# DLPG_main_v3.net
KiCad netlist of a schematic drawn in EAGLE
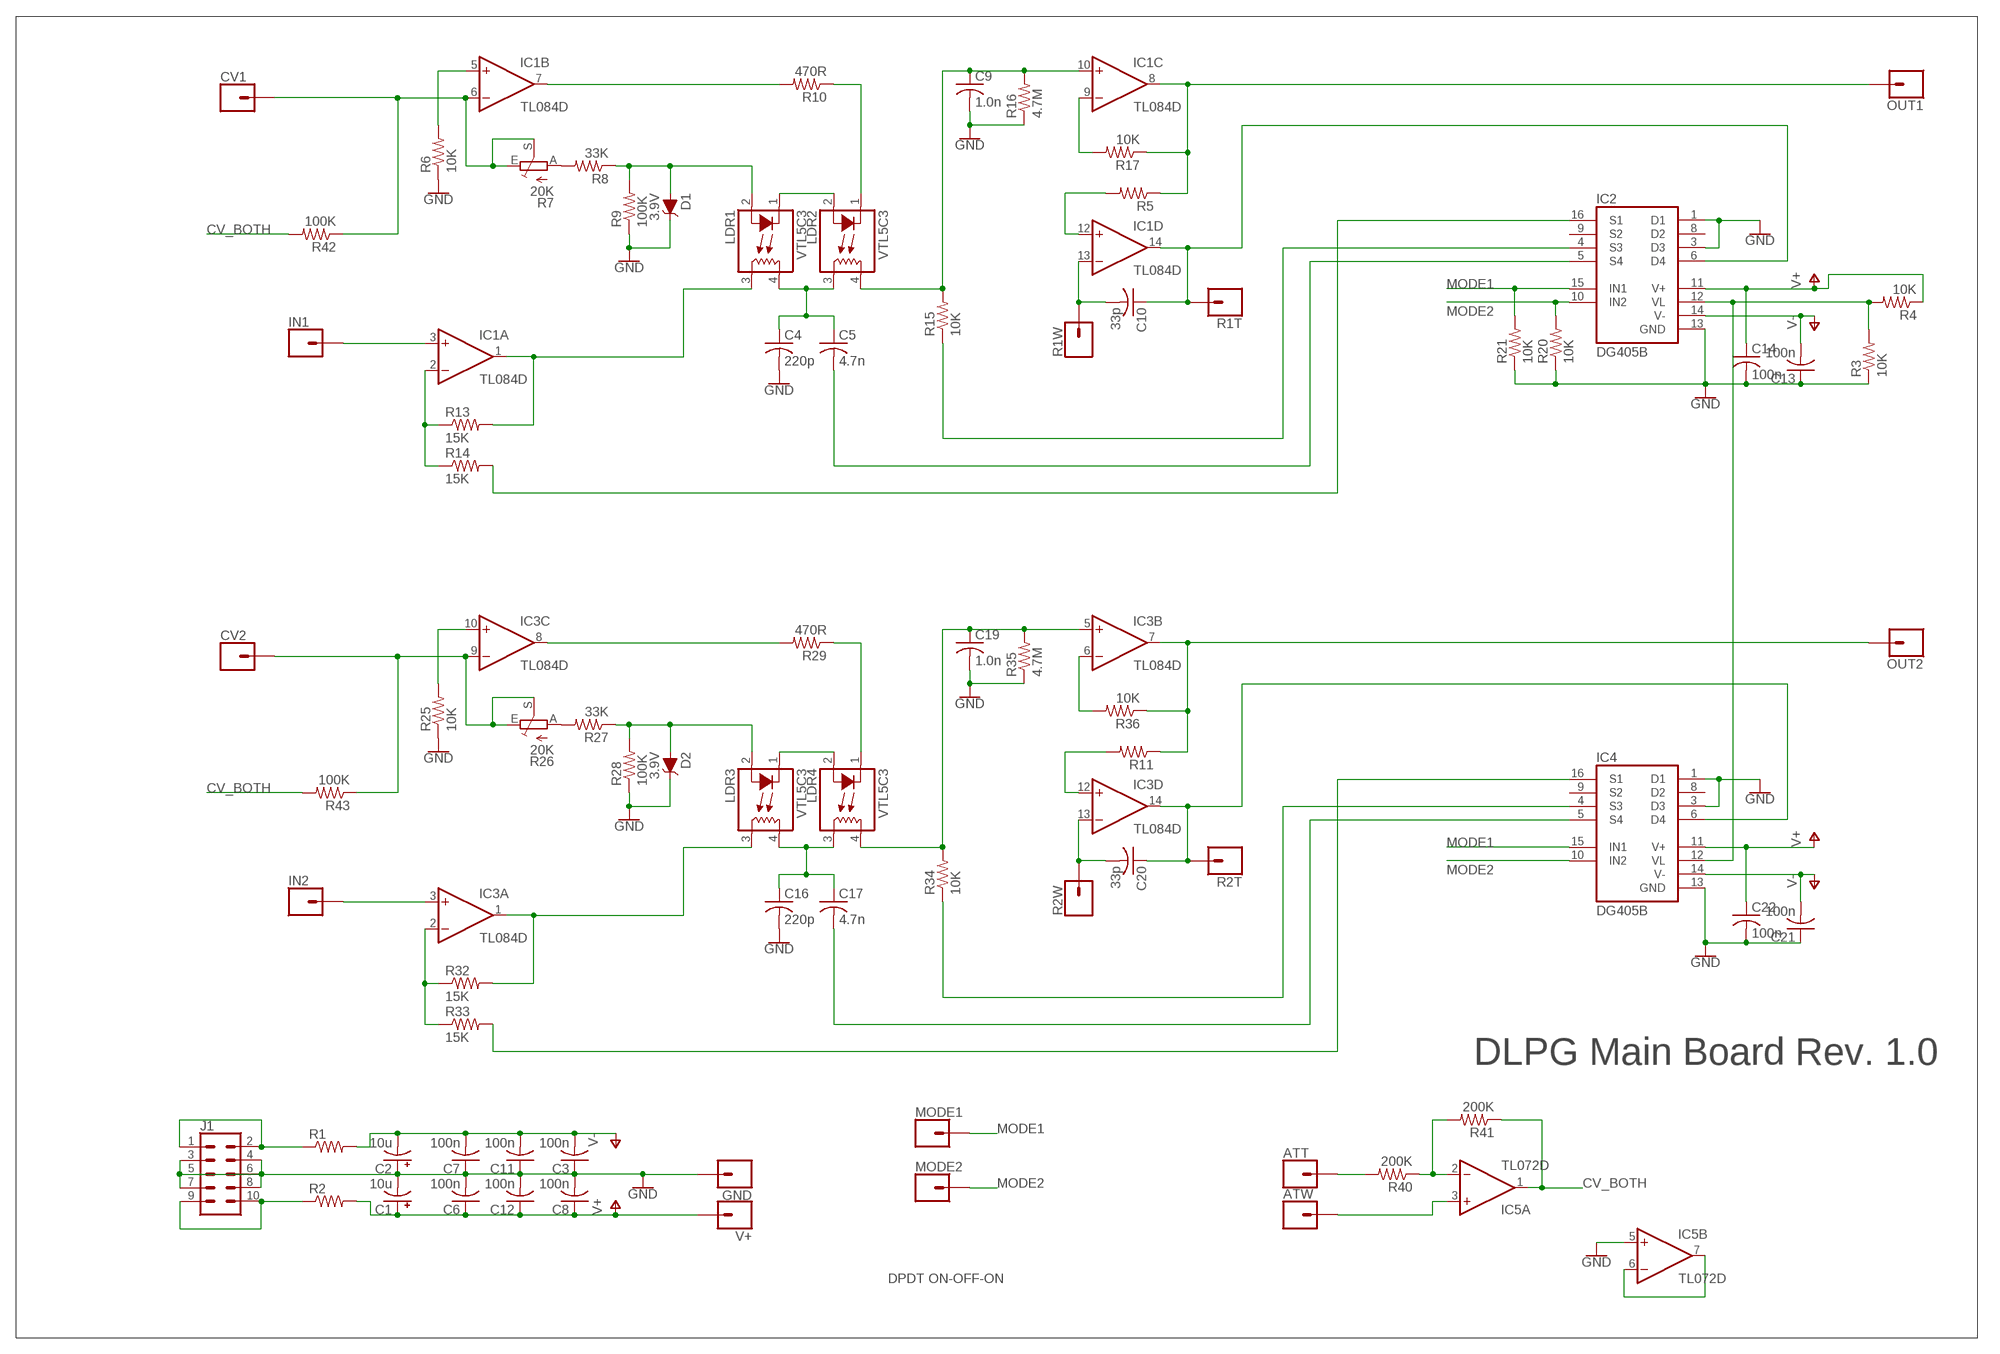
[diagram p0: schematic, sheet 1]

(export (version "E")
  (design (tool "Eeschema 10.0.6"))
  (components
    (comp (ref "ATT")
      (value "CONN_01")
      (footprint "eagle-import:1X01")
      (libsource (lib "eagle-import") (part "CONN_01"))
    )
    (comp (ref "ATW")
      (value "CONN_01")
      (footprint "eagle-import:1X01")
      (libsource (lib "eagle-import") (part "CONN_01"))
    )
    (comp (ref "C1")
      (value "10u")
      (footprint "eagle-import:PANASONIC_C")
      (libsource (lib "eagle-import") (part "CAP_POLC"))
    )
    (comp (ref "C2")
      (value "10u")
      (footprint "eagle-import:PANASONIC_C")
      (libsource (lib "eagle-import") (part "CAP_POLC"))
    )
    (comp (ref "C3")
      (value "100n")
      (footprint "eagle-import:C0805K")
      (libsource (lib "eagle-import") (part "C-USC0805K"))
    )
    (comp (ref "C4")
      (value "220p")
      (footprint "eagle-import:C0805K")
      (libsource (lib "eagle-import") (part "C-USC0805K"))
    )
    (comp (ref "C5")
      (value "4.7n")
      (footprint "eagle-import:C0805K")
      (libsource (lib "eagle-import") (part "C-USC0805K"))
    )
    (comp (ref "C6")
      (value "100n")
      (footprint "eagle-import:C0805K")
      (libsource (lib "eagle-import") (part "C-USC0805K"))
    )
    (comp (ref "C7")
      (value "100n")
      (footprint "eagle-import:C0805K")
      (libsource (lib "eagle-import") (part "C-USC0805K"))
    )
    (comp (ref "C8")
      (value "100n")
      (footprint "eagle-import:C0805K")
      (libsource (lib "eagle-import") (part "C-USC0805K"))
    )
    (comp (ref "C9")
      (value "1.0n")
      (footprint "eagle-import:C0805K")
      (libsource (lib "eagle-import") (part "C-USC0805K"))
    )
    (comp (ref "C10")
      (value "33p")
      (footprint "eagle-import:C0805K")
      (libsource (lib "eagle-import") (part "C-USC0805K"))
    )
    (comp (ref "C11")
      (value "100n")
      (footprint "eagle-import:C0805K")
      (libsource (lib "eagle-import") (part "C-USC0805K"))
    )
    (comp (ref "C12")
      (value "100n")
      (footprint "eagle-import:C0805K")
      (libsource (lib "eagle-import") (part "C-USC0805K"))
    )
    (comp (ref "C13")
      (value "100n")
      (footprint "eagle-import:C0805K")
      (libsource (lib "eagle-import") (part "C-USC0805K"))
    )
    (comp (ref "C14")
      (value "100n")
      (footprint "eagle-import:C0805K")
      (libsource (lib "eagle-import") (part "C-USC0805K"))
    )
    (comp (ref "C16")
      (value "220p")
      (footprint "eagle-import:C0805K")
      (libsource (lib "eagle-import") (part "C-USC0805K"))
    )
    (comp (ref "C17")
      (value "4.7n")
      (footprint "eagle-import:C0805K")
      (libsource (lib "eagle-import") (part "C-USC0805K"))
    )
    (comp (ref "C19")
      (value "1.0n")
      (footprint "eagle-import:C0805K")
      (libsource (lib "eagle-import") (part "C-USC0805K"))
    )
    (comp (ref "C20")
      (value "33p")
      (footprint "eagle-import:C0805K")
      (libsource (lib "eagle-import") (part "C-USC0805K"))
    )
    (comp (ref "C21")
      (value "100n")
      (footprint "eagle-import:C0805K")
      (libsource (lib "eagle-import") (part "C-USC0805K"))
    )
    (comp (ref "C22")
      (value "100n")
      (footprint "eagle-import:C0805K")
      (libsource (lib "eagle-import") (part "C-USC0805K"))
    )
    (comp (ref "CV1")
      (value "CONN_01")
      (footprint "eagle-import:1X01")
      (libsource (lib "eagle-import") (part "CONN_01"))
    )
    (comp (ref "CV2")
      (value "CONN_01")
      (footprint "eagle-import:1X01")
      (libsource (lib "eagle-import") (part "CONN_01"))
    )
    (comp (ref "D1")
      (value "3.9V")
      (footprint "eagle-import:SOD-323")
      (libsource (lib "eagle-import") (part "DIODE-ZENER-MM3Z3V3T1G"))
    )
    (comp (ref "D2")
      (value "3.9V")
      (footprint "eagle-import:SOD-323")
      (libsource (lib "eagle-import") (part "DIODE-ZENER-MM3Z3V3T1G"))
    )
    (comp (ref "GND")
      (value "CONN_01")
      (footprint "eagle-import:1X01")
      (libsource (lib "eagle-import") (part "CONN_01"))
    )
    (comp (ref "IC1")
      (value "TL084D")
      (footprint "eagle-import:SO14")
      (libsource (lib "eagle-import") (part "TL084D"))
    )
    (comp (ref "IC2")
      (value "DG405B")
      (footprint "eagle-import:SO16")
      (fields (field (name "MPN") "DG405CY+"))
      (libsource (lib "eagle-import") (part "DG405CY"))
    )
    (comp (ref "IC3")
      (value "TL084D")
      (footprint "eagle-import:SO14")
      (libsource (lib "eagle-import") (part "TL084D"))
    )
    (comp (ref "IC4")
      (value "DG405B")
      (footprint "eagle-import:SO16")
      (fields (field (name "MPN") "DG405CY+"))
      (libsource (lib "eagle-import") (part "DG405CY"))
    )
    (comp (ref "IC5")
      (value "TL072D")
      (footprint "eagle-import:SO08")
      (libsource (lib "eagle-import") (part "TL072D"))
    )
    (comp (ref "IN1")
      (value "CONN_01")
      (footprint "eagle-import:1X01")
      (libsource (lib "eagle-import") (part "CONN_01"))
    )
    (comp (ref "IN2")
      (value "CONN_01")
      (footprint "eagle-import:1X01")
      (libsource (lib "eagle-import") (part "CONN_01"))
    )
    (comp (ref "J1")
      (value "CONN_05X2PTH")
      (footprint "eagle-import:2X5")
      (libsource (lib "eagle-import") (part "CONN_05X2PTH"))
    )
    (comp (ref "LDR1")
      (value "VTL5C3")
      (footprint "eagle-import:VTL5C")
      (fields (field (name "MF") "VACTEC PHOTO") (field (name "MPN") "VTL5C9"))
      (libsource (lib "eagle-import") (part "VTL5C9"))
    )
    (comp (ref "LDR2")
      (value "VTL5C3")
      (footprint "eagle-import:VTL5C")
      (fields (field (name "MF") "VACTEC PHOTO") (field (name "MPN") "VTL5C9"))
      (libsource (lib "eagle-import") (part "VTL5C9"))
    )
    (comp (ref "LDR3")
      (value "VTL5C3")
      (footprint "eagle-import:VTL5C")
      (fields (field (name "MF") "VACTEC PHOTO") (field (name "MPN") "VTL5C9"))
      (libsource (lib "eagle-import") (part "VTL5C9"))
    )
    (comp (ref "LDR4")
      (value "VTL5C3")
      (footprint "eagle-import:VTL5C")
      (fields (field (name "MF") "VACTEC PHOTO") (field (name "MPN") "VTL5C9"))
      (libsource (lib "eagle-import") (part "VTL5C9"))
    )
    (comp (ref "MODE1")
      (value "CONN_01")
      (footprint "eagle-import:1X01")
      (libsource (lib "eagle-import") (part "CONN_01"))
    )
    (comp (ref "MODE2")
      (value "CONN_01")
      (footprint "eagle-import:1X01")
      (libsource (lib "eagle-import") (part "CONN_01"))
    )
    (comp (ref "OUT1")
      (value "CONN_01")
      (footprint "eagle-import:1X01")
      (libsource (lib "eagle-import") (part "CONN_01"))
    )
    (comp (ref "OUT2")
      (value "CONN_01")
      (footprint "eagle-import:1X01")
      (libsource (lib "eagle-import") (part "CONN_01"))
    )
    (comp (ref "R1")
      (value "RESISTOR0805-RES")
      (footprint "eagle-import:0805")
      (libsource (lib "eagle-import") (part "RESISTOR0805-RES"))
    )
    (comp (ref "R1T")
      (value "CONN_01")
      (footprint "eagle-import:1X01")
      (libsource (lib "eagle-import") (part "CONN_01"))
    )
    (comp (ref "R1W")
      (value "CONN_01")
      (footprint "eagle-import:1X01")
      (libsource (lib "eagle-import") (part "CONN_01"))
    )
    (comp (ref "R2")
      (value "RESISTOR0805-RES")
      (footprint "eagle-import:0805")
      (libsource (lib "eagle-import") (part "RESISTOR0805-RES"))
    )
    (comp (ref "R2T")
      (value "CONN_01")
      (footprint "eagle-import:1X01")
      (libsource (lib "eagle-import") (part "CONN_01"))
    )
    (comp (ref "R2W")
      (value "CONN_01")
      (footprint "eagle-import:1X01")
      (libsource (lib "eagle-import") (part "CONN_01"))
    )
    (comp (ref "R3")
      (value "10K")
      (footprint "eagle-import:M0805")
      (libsource (lib "eagle-import") (part "R-US_M0805"))
    )
    (comp (ref "R4")
      (value "10K")
      (footprint "eagle-import:M0805")
      (libsource (lib "eagle-import") (part "R-US_M0805"))
    )
    (comp (ref "R5")
      (value "R-US_M0805")
      (footprint "eagle-import:M0805")
      (libsource (lib "eagle-import") (part "R-US_M0805"))
    )
    (comp (ref "R6")
      (value "10K")
      (footprint "eagle-import:M0805")
      (libsource (lib "eagle-import") (part "R-US_M0805"))
    )
    (comp (ref "R7")
      (value "20K")
      (footprint "eagle-import:S64YW")
      (libsource (lib "eagle-import") (part "TRIM_1234-S64YW"))
    )
    (comp (ref "R8")
      (value "33K")
      (footprint "eagle-import:M0805")
      (libsource (lib "eagle-import") (part "R-US_M0805"))
    )
    (comp (ref "R9")
      (value "100K")
      (footprint "eagle-import:M0805")
      (libsource (lib "eagle-import") (part "R-US_M0805"))
    )
    (comp (ref "R10")
      (value "470R")
      (footprint "eagle-import:M0805")
      (libsource (lib "eagle-import") (part "R-US_M0805"))
    )
    (comp (ref "R11")
      (value "R-US_M0805")
      (footprint "eagle-import:M0805")
      (libsource (lib "eagle-import") (part "R-US_M0805"))
    )
    (comp (ref "R13")
      (value "15K")
      (footprint "eagle-import:M0805")
      (libsource (lib "eagle-import") (part "R-US_M0805"))
    )
    (comp (ref "R14")
      (value "15K")
      (footprint "eagle-import:M0805")
      (libsource (lib "eagle-import") (part "R-US_M0805"))
    )
    (comp (ref "R15")
      (value "10K")
      (footprint "eagle-import:M0805")
      (libsource (lib "eagle-import") (part "R-US_M0805"))
    )
    (comp (ref "R16")
      (value "4.7M")
      (footprint "eagle-import:M0805")
      (libsource (lib "eagle-import") (part "R-US_M0805"))
    )
    (comp (ref "R17")
      (value "10K")
      (footprint "eagle-import:M0805")
      (libsource (lib "eagle-import") (part "R-US_M0805"))
    )
    (comp (ref "R20")
      (value "10K")
      (footprint "eagle-import:M0805")
      (libsource (lib "eagle-import") (part "R-US_M0805"))
    )
    (comp (ref "R21")
      (value "10K")
      (footprint "eagle-import:M0805")
      (libsource (lib "eagle-import") (part "R-US_M0805"))
    )
    (comp (ref "R25")
      (value "10K")
      (footprint "eagle-import:M0805")
      (libsource (lib "eagle-import") (part "R-US_M0805"))
    )
    (comp (ref "R26")
      (value "20K")
      (footprint "eagle-import:S64YW")
      (libsource (lib "eagle-import") (part "TRIM_1234-S64YW"))
    )
    (comp (ref "R27")
      (value "33K")
      (footprint "eagle-import:M0805")
      (libsource (lib "eagle-import") (part "R-US_M0805"))
    )
    (comp (ref "R28")
      (value "100K")
      (footprint "eagle-import:M0805")
      (libsource (lib "eagle-import") (part "R-US_M0805"))
    )
    (comp (ref "R29")
      (value "470R")
      (footprint "eagle-import:M0805")
      (libsource (lib "eagle-import") (part "R-US_M0805"))
    )
    (comp (ref "R32")
      (value "15K")
      (footprint "eagle-import:M0805")
      (libsource (lib "eagle-import") (part "R-US_M0805"))
    )
    (comp (ref "R33")
      (value "15K")
      (footprint "eagle-import:M0805")
      (libsource (lib "eagle-import") (part "R-US_M0805"))
    )
    (comp (ref "R34")
      (value "10K")
      (footprint "eagle-import:M0805")
      (libsource (lib "eagle-import") (part "R-US_M0805"))
    )
    (comp (ref "R35")
      (value "4.7M")
      (footprint "eagle-import:M0805")
      (libsource (lib "eagle-import") (part "R-US_M0805"))
    )
    (comp (ref "R36")
      (value "10K")
      (footprint "eagle-import:M0805")
      (libsource (lib "eagle-import") (part "R-US_M0805"))
    )
    (comp (ref "R40")
      (value "200K")
      (footprint "eagle-import:M0805")
      (libsource (lib "eagle-import") (part "R-US_M0805"))
    )
    (comp (ref "R41")
      (value "200K")
      (footprint "eagle-import:M0805")
      (libsource (lib "eagle-import") (part "R-US_M0805"))
    )
    (comp (ref "R42")
      (value "100K")
      (footprint "eagle-import:M0805")
      (libsource (lib "eagle-import") (part "R-US_M0805"))
    )
    (comp (ref "R43")
      (value "100K")
      (footprint "eagle-import:M0805")
      (libsource (lib "eagle-import") (part "R-US_M0805"))
    )
    (comp (ref "V+")
      (value "CONN_01")
      (footprint "eagle-import:1X01")
      (libsource (lib "eagle-import") (part "CONN_01"))
    )
  )
  (nets
    (net (code "1") (name "/CV_BOTH") (class "Default")
      (node (ref "IC5") (pin "1") (pinfunction "OUT_1") (pintype "output"))
      (node (ref "R41") (pin "1") (pinfunction "1_1") (pintype "passive"))
      (node (ref "R42") (pin "2") (pinfunction "2_2") (pintype "passive"))
      (node (ref "R43") (pin "2") (pinfunction "2_2") (pintype "passive"))
    )
    (net (code "2") (name "/MODE1") (class "Default")
      (node (ref "IC2") (pin "15") (pinfunction "IN1_15") (pintype "input"))
      (node (ref "IC4") (pin "15") (pinfunction "IN1_15") (pintype "input"))
      (node (ref "MODE1") (pin "1") (pinfunction "1_1") (pintype "passive"))
      (node (ref "R21") (pin "2") (pinfunction "2_2") (pintype "passive"))
    )
    (net (code "3") (name "/MODE2") (class "Default")
      (node (ref "IC2") (pin "10") (pinfunction "IN2_10") (pintype "input"))
      (node (ref "IC4") (pin "10") (pinfunction "IN2_10") (pintype "input"))
      (node (ref "MODE2") (pin "1") (pinfunction "1_1") (pintype "passive"))
      (node (ref "R20") (pin "2") (pinfunction "2_2") (pintype "passive"))
    )
    (net (code "4") (name "GND") (class "Default")
      (node (ref "C1") (pin "-") (pinfunction "-_-") (pintype "passive"))
      (node (ref "C11") (pin "1") (pinfunction "1_1") (pintype "passive"))
      (node (ref "C12") (pin "2") (pinfunction "2_2") (pintype "passive"))
      (node (ref "C13") (pin "1") (pinfunction "1_1") (pintype "passive"))
      (node (ref "C14") (pin "2") (pinfunction "2_2") (pintype "passive"))
      (node (ref "C16") (pin "2") (pinfunction "2_2") (pintype "passive"))
      (node (ref "C19") (pin "2") (pinfunction "2_2") (pintype "passive"))
      (node (ref "C2") (pin "+") (pinfunction "+_+") (pintype "passive"))
      (node (ref "C21") (pin "1") (pinfunction "1_1") (pintype "passive"))
      (node (ref "C22") (pin "2") (pinfunction "2_2") (pintype "passive"))
      (node (ref "C3") (pin "1") (pinfunction "1_1") (pintype "passive"))
      (node (ref "C4") (pin "2") (pinfunction "2_2") (pintype "passive"))
      (node (ref "C6") (pin "2") (pinfunction "2_2") (pintype "passive"))
      (node (ref "C7") (pin "1") (pinfunction "1_1") (pintype "passive"))
      (node (ref "C8") (pin "2") (pinfunction "2_2") (pintype "passive"))
      (node (ref "C9") (pin "2") (pinfunction "2_2") (pintype "passive"))
      (node (ref "D1") (pin "C") (pinfunction "C_C") (pintype "passive"))
      (node (ref "D2") (pin "C") (pinfunction "C_C") (pintype "passive"))
      (node (ref "GND") (pin "1") (pinfunction "1_1") (pintype "passive"))
      (node (ref "IC2") (pin "1") (pinfunction "D1_1") (pintype "passive"))
      (node (ref "IC2") (pin "13") (pinfunction "GND_13") (pintype "power_in"))
      (node (ref "IC2") (pin "3") (pinfunction "D3_3") (pintype "passive"))
      (node (ref "IC4") (pin "1") (pinfunction "D1_1") (pintype "passive"))
      (node (ref "IC4") (pin "13") (pinfunction "GND_13") (pintype "power_in"))
      (node (ref "IC4") (pin "3") (pinfunction "D3_3") (pintype "passive"))
      (node (ref "IC5") (pin "5") (pinfunction "+IN_5") (pintype "input"))
      (node (ref "J1") (pin "3") (pinfunction "3_3") (pintype "passive"))
      (node (ref "J1") (pin "4") (pinfunction "4_4") (pintype "passive"))
      (node (ref "J1") (pin "5") (pinfunction "5_5") (pintype "passive"))
      (node (ref "J1") (pin "6") (pinfunction "6_6") (pintype "passive"))
      (node (ref "J1") (pin "7") (pinfunction "7_7") (pintype "passive"))
      (node (ref "J1") (pin "8") (pinfunction "8_8") (pintype "passive"))
      (node (ref "R16") (pin "1") (pinfunction "1_1") (pintype "passive"))
      (node (ref "R20") (pin "1") (pinfunction "1_1") (pintype "passive"))
      (node (ref "R21") (pin "1") (pinfunction "1_1") (pintype "passive"))
      (node (ref "R25") (pin "1") (pinfunction "1_1") (pintype "passive"))
      (node (ref "R28") (pin "1") (pinfunction "1_1") (pintype "passive"))
      (node (ref "R3") (pin "1") (pinfunction "1_1") (pintype "passive"))
      (node (ref "R35") (pin "1") (pinfunction "1_1") (pintype "passive"))
      (node (ref "R6") (pin "1") (pinfunction "1_1") (pintype "passive"))
      (node (ref "R9") (pin "1") (pinfunction "1_1") (pintype "passive"))
    )
    (net (code "5") (name "Net-(ATT-Pad1)") (class "Default")
      (node (ref "ATT") (pin "1") (pinfunction "1_1") (pintype "passive"))
      (node (ref "R40") (pin "2") (pinfunction "2_2") (pintype "passive"))
    )
    (net (code "6") (name "Net-(IC1A-+IN)") (class "Default")
      (node (ref "IC1") (pin "3") (pinfunction "+IN_3") (pintype "input"))
      (node (ref "IN1") (pin "1") (pinfunction "1_1") (pintype "passive"))
    )
    (net (code "7") (name "Net-(IC1A--IN)") (class "Default")
      (node (ref "IC1") (pin "2") (pinfunction "-IN_2") (pintype "input"))
      (node (ref "R13") (pin "1") (pinfunction "1_1") (pintype "passive"))
      (node (ref "R14") (pin "1") (pinfunction "1_1") (pintype "passive"))
    )
    (net (code "8") (name "Net-(IC1A-OUT)") (class "Default")
      (node (ref "IC1") (pin "1") (pinfunction "OUT_1") (pintype "output"))
      (node (ref "LDR1") (pin "3") (pinfunction "L1_3") (pintype "passive"))
      (node (ref "R13") (pin "2") (pinfunction "2_2") (pintype "passive"))
    )
    (net (code "9") (name "Net-(IC1B-+IN)") (class "Default")
      (node (ref "IC1") (pin "5") (pinfunction "+IN_5") (pintype "input"))
      (node (ref "R6") (pin "2") (pinfunction "2_2") (pintype "passive"))
    )
    (net (code "10") (name "Net-(IC1B--IN)") (class "Default")
      (node (ref "CV1") (pin "1") (pinfunction "1_1") (pintype "passive"))
      (node (ref "IC1") (pin "6") (pinfunction "-IN_6") (pintype "input"))
      (node (ref "R42") (pin "1") (pinfunction "1_1") (pintype "passive"))
      (node (ref "R7") (pin "E") (pinfunction "E_E") (pintype "passive"))
      (node (ref "R7") (pin "S") (pinfunction "S_S") (pintype "passive"))
    )
    (net (code "11") (name "Net-(IC1B-OUT)") (class "Default")
      (node (ref "IC1") (pin "7") (pinfunction "OUT_7") (pintype "output"))
      (node (ref "R10") (pin "2") (pinfunction "2_2") (pintype "passive"))
    )
    (net (code "12") (name "Net-(IC1C-+IN)") (class "Default")
      (node (ref "C9") (pin "1") (pinfunction "1_1") (pintype "passive"))
      (node (ref "IC1") (pin "10") (pinfunction "+IN_10") (pintype "input"))
      (node (ref "LDR2") (pin "4") (pinfunction "L2_4") (pintype "passive"))
      (node (ref "R15") (pin "2") (pinfunction "2_2") (pintype "passive"))
      (node (ref "R16") (pin "2") (pinfunction "2_2") (pintype "passive"))
    )
    (net (code "13") (name "Net-(IC1C--IN)") (class "Default")
      (node (ref "IC1") (pin "9") (pinfunction "-IN_9") (pintype "input"))
      (node (ref "R17") (pin "2") (pinfunction "2_2") (pintype "passive"))
    )
    (net (code "14") (name "Net-(IC1C-OUT)") (class "Default")
      (node (ref "IC1") (pin "8") (pinfunction "OUT_8") (pintype "output"))
      (node (ref "OUT1") (pin "1") (pinfunction "1_1") (pintype "passive"))
      (node (ref "R17") (pin "1") (pinfunction "1_1") (pintype "passive"))
      (node (ref "R5") (pin "1") (pinfunction "1_1") (pintype "passive"))
    )
    (net (code "15") (name "Net-(IC1D-+IN)") (class "Default")
      (node (ref "IC1") (pin "12") (pinfunction "+IN_12") (pintype "input"))
      (node (ref "R5") (pin "2") (pinfunction "2_2") (pintype "passive"))
    )
    (net (code "16") (name "Net-(IC1D--IN)") (class "Default")
      (node (ref "C10") (pin "2") (pinfunction "2_2") (pintype "passive"))
      (node (ref "IC1") (pin "13") (pinfunction "-IN_13") (pintype "input"))
      (node (ref "R1W") (pin "1") (pinfunction "1_1") (pintype "passive"))
    )
    (net (code "17") (name "Net-(IC1D-OUT)") (class "Default")
      (node (ref "C10") (pin "1") (pinfunction "1_1") (pintype "passive"))
      (node (ref "IC1") (pin "14") (pinfunction "OUT_14") (pintype "output"))
      (node (ref "IC2") (pin "6") (pinfunction "D4_6") (pintype "passive"))
      (node (ref "R1T") (pin "1") (pinfunction "1_1") (pintype "passive"))
    )
    (net (code "18") (name "Net-(IC2-S1)") (class "Default")
      (node (ref "IC2") (pin "16") (pinfunction "S1_16") (pintype "passive"))
      (node (ref "R14") (pin "2") (pinfunction "2_2") (pintype "passive"))
    )
    (net (code "19") (name "Net-(IC2-S3)") (class "Default")
      (node (ref "IC2") (pin "4") (pinfunction "S3_4") (pintype "passive"))
      (node (ref "R15") (pin "1") (pinfunction "1_1") (pintype "passive"))
    )
    (net (code "20") (name "Net-(IC2-S4)") (class "Default")
      (node (ref "C5") (pin "2") (pinfunction "2_2") (pintype "passive"))
      (node (ref "IC2") (pin "5") (pinfunction "S4_5") (pintype "passive"))
    )
    (net (code "21") (name "Net-(IC2-VL)") (class "Default")
      (node (ref "IC2") (pin "12") (pinfunction "VL_12") (pintype "power_in"))
      (node (ref "IC4") (pin "12") (pinfunction "VL_12") (pintype "power_in"))
      (node (ref "R3") (pin "2") (pinfunction "2_2") (pintype "passive"))
      (node (ref "R4") (pin "2") (pinfunction "2_2") (pintype "passive"))
    )
    (net (code "22") (name "Net-(IC3A-+IN)") (class "Default")
      (node (ref "IC3") (pin "3") (pinfunction "+IN_3") (pintype "input"))
      (node (ref "IN2") (pin "1") (pinfunction "1_1") (pintype "passive"))
    )
    (net (code "23") (name "Net-(IC3A--IN)") (class "Default")
      (node (ref "IC3") (pin "2") (pinfunction "-IN_2") (pintype "input"))
      (node (ref "R32") (pin "1") (pinfunction "1_1") (pintype "passive"))
      (node (ref "R33") (pin "1") (pinfunction "1_1") (pintype "passive"))
    )
    (net (code "24") (name "Net-(IC3A-OUT)") (class "Default")
      (node (ref "IC3") (pin "1") (pinfunction "OUT_1") (pintype "output"))
      (node (ref "LDR3") (pin "3") (pinfunction "L1_3") (pintype "passive"))
      (node (ref "R32") (pin "2") (pinfunction "2_2") (pintype "passive"))
    )
    (net (code "25") (name "Net-(IC3B-+IN)") (class "Default")
      (node (ref "C19") (pin "1") (pinfunction "1_1") (pintype "passive"))
      (node (ref "IC3") (pin "5") (pinfunction "+IN_5") (pintype "input"))
      (node (ref "LDR4") (pin "4") (pinfunction "L2_4") (pintype "passive"))
      (node (ref "R34") (pin "2") (pinfunction "2_2") (pintype "passive"))
      (node (ref "R35") (pin "2") (pinfunction "2_2") (pintype "passive"))
    )
    (net (code "26") (name "Net-(IC3B--IN)") (class "Default")
      (node (ref "IC3") (pin "6") (pinfunction "-IN_6") (pintype "input"))
      (node (ref "R36") (pin "2") (pinfunction "2_2") (pintype "passive"))
    )
    (net (code "27") (name "Net-(IC3B-OUT)") (class "Default")
      (node (ref "IC3") (pin "7") (pinfunction "OUT_7") (pintype "output"))
      (node (ref "OUT2") (pin "1") (pinfunction "1_1") (pintype "passive"))
      (node (ref "R11") (pin "1") (pinfunction "1_1") (pintype "passive"))
      (node (ref "R36") (pin "1") (pinfunction "1_1") (pintype "passive"))
    )
    (net (code "28") (name "Net-(IC3C-+IN)") (class "Default")
      (node (ref "IC3") (pin "10") (pinfunction "+IN_10") (pintype "input"))
      (node (ref "R25") (pin "2") (pinfunction "2_2") (pintype "passive"))
    )
    (net (code "29") (name "Net-(IC3C--IN)") (class "Default")
      (node (ref "CV2") (pin "1") (pinfunction "1_1") (pintype "passive"))
      (node (ref "IC3") (pin "9") (pinfunction "-IN_9") (pintype "input"))
      (node (ref "R26") (pin "E") (pinfunction "E_E") (pintype "passive"))
      (node (ref "R26") (pin "S") (pinfunction "S_S") (pintype "passive"))
      (node (ref "R43") (pin "1") (pinfunction "1_1") (pintype "passive"))
    )
    (net (code "30") (name "Net-(IC3C-OUT)") (class "Default")
      (node (ref "IC3") (pin "8") (pinfunction "OUT_8") (pintype "output"))
      (node (ref "R29") (pin "2") (pinfunction "2_2") (pintype "passive"))
    )
    (net (code "31") (name "Net-(IC3D-+IN)") (class "Default")
      (node (ref "IC3") (pin "12") (pinfunction "+IN_12") (pintype "input"))
      (node (ref "R11") (pin "2") (pinfunction "2_2") (pintype "passive"))
    )
    (net (code "32") (name "Net-(IC3D--IN)") (class "Default")
      (node (ref "C20") (pin "2") (pinfunction "2_2") (pintype "passive"))
      (node (ref "IC3") (pin "13") (pinfunction "-IN_13") (pintype "input"))
      (node (ref "R2W") (pin "1") (pinfunction "1_1") (pintype "passive"))
    )
    (net (code "33") (name "Net-(IC3D-OUT)") (class "Default")
      (node (ref "C20") (pin "1") (pinfunction "1_1") (pintype "passive"))
      (node (ref "IC3") (pin "14") (pinfunction "OUT_14") (pintype "output"))
      (node (ref "IC4") (pin "6") (pinfunction "D4_6") (pintype "passive"))
      (node (ref "R2T") (pin "1") (pinfunction "1_1") (pintype "passive"))
    )
    (net (code "34") (name "Net-(IC4-S1)") (class "Default")
      (node (ref "IC4") (pin "16") (pinfunction "S1_16") (pintype "passive"))
      (node (ref "R33") (pin "2") (pinfunction "2_2") (pintype "passive"))
    )
    (net (code "35") (name "Net-(IC4-S3)") (class "Default")
      (node (ref "IC4") (pin "4") (pinfunction "S3_4") (pintype "passive"))
      (node (ref "R34") (pin "1") (pinfunction "1_1") (pintype "passive"))
    )
    (net (code "36") (name "Net-(IC4-S4)") (class "Default")
      (node (ref "C17") (pin "2") (pinfunction "2_2") (pintype "passive"))
      (node (ref "IC4") (pin "5") (pinfunction "S4_5") (pintype "passive"))
    )
    (net (code "37") (name "Net-(IC5A-+IN)") (class "Default")
      (node (ref "ATW") (pin "1") (pinfunction "1_1") (pintype "passive"))
      (node (ref "IC5") (pin "3") (pinfunction "+IN_3") (pintype "input"))
    )
    (net (code "38") (name "Net-(IC5A--IN)") (class "Default")
      (node (ref "IC5") (pin "2") (pinfunction "-IN_2") (pintype "input"))
      (node (ref "R40") (pin "1") (pinfunction "1_1") (pintype "passive"))
      (node (ref "R41") (pin "2") (pinfunction "2_2") (pintype "passive"))
    )
    (net (code "39") (name "Net-(IC5B--IN)") (class "Default")
      (node (ref "IC5") (pin "6") (pinfunction "-IN_6") (pintype "input"))
      (node (ref "IC5") (pin "7") (pinfunction "OUT_7") (pintype "output"))
    )
    (net (code "40") (name "Net-(J1-Pad1)") (class "Default")
      (node (ref "J1") (pin "1") (pinfunction "1_1") (pintype "passive"))
      (node (ref "J1") (pin "2") (pinfunction "2_2") (pintype "passive"))
      (node (ref "R1") (pin "1") (pinfunction "1_1") (pintype "passive"))
    )
    (net (code "41") (name "Net-(J1-Pad10)") (class "Default")
      (node (ref "J1") (pin "10") (pinfunction "10_10") (pintype "passive"))
      (node (ref "J1") (pin "9") (pinfunction "9_9") (pintype "passive"))
      (node (ref "R2") (pin "1") (pinfunction "1_1") (pintype "passive"))
    )
    (net (code "42") (name "Net-(LDR1-A)") (class "Default")
      (node (ref "D1") (pin "A") (pinfunction "A_A") (pintype "passive"))
      (node (ref "LDR1") (pin "2") (pinfunction "A_2") (pintype "passive"))
      (node (ref "R8") (pin "1") (pinfunction "1_1") (pintype "passive"))
      (node (ref "R9") (pin "2") (pinfunction "2_2") (pintype "passive"))
    )
    (net (code "43") (name "Net-(LDR1-C)") (class "Default")
      (node (ref "LDR1") (pin "1") (pinfunction "C_1") (pintype "passive"))
      (node (ref "LDR2") (pin "2") (pinfunction "A_2") (pintype "passive"))
    )
    (net (code "44") (name "Net-(LDR1-L2)") (class "Default")
      (node (ref "C4") (pin "1") (pinfunction "1_1") (pintype "passive"))
      (node (ref "C5") (pin "1") (pinfunction "1_1") (pintype "passive"))
      (node (ref "LDR1") (pin "4") (pinfunction "L2_4") (pintype "passive"))
      (node (ref "LDR2") (pin "3") (pinfunction "L1_3") (pintype "passive"))
    )
    (net (code "45") (name "Net-(LDR2-C)") (class "Default")
      (node (ref "LDR2") (pin "1") (pinfunction "C_1") (pintype "passive"))
      (node (ref "R10") (pin "1") (pinfunction "1_1") (pintype "passive"))
    )
    (net (code "46") (name "Net-(LDR3-A)") (class "Default")
      (node (ref "D2") (pin "A") (pinfunction "A_A") (pintype "passive"))
      (node (ref "LDR3") (pin "2") (pinfunction "A_2") (pintype "passive"))
      (node (ref "R27") (pin "1") (pinfunction "1_1") (pintype "passive"))
      (node (ref "R28") (pin "2") (pinfunction "2_2") (pintype "passive"))
    )
    (net (code "47") (name "Net-(LDR3-C)") (class "Default")
      (node (ref "LDR3") (pin "1") (pinfunction "C_1") (pintype "passive"))
      (node (ref "LDR4") (pin "2") (pinfunction "A_2") (pintype "passive"))
    )
    (net (code "48") (name "Net-(LDR3-L2)") (class "Default")
      (node (ref "C16") (pin "1") (pinfunction "1_1") (pintype "passive"))
      (node (ref "C17") (pin "1") (pinfunction "1_1") (pintype "passive"))
      (node (ref "LDR3") (pin "4") (pinfunction "L2_4") (pintype "passive"))
      (node (ref "LDR4") (pin "3") (pinfunction "L1_3") (pintype "passive"))
    )
    (net (code "49") (name "Net-(LDR4-C)") (class "Default")
      (node (ref "LDR4") (pin "1") (pinfunction "C_1") (pintype "passive"))
      (node (ref "R29") (pin "1") (pinfunction "1_1") (pintype "passive"))
    )
    (net (code "50") (name "Net-(R7-PadA)") (class "Default")
      (node (ref "R7") (pin "A") (pinfunction "A_A") (pintype "passive"))
      (node (ref "R8") (pin "2") (pinfunction "2_2") (pintype "passive"))
    )
    (net (code "51") (name "Net-(R26-PadA)") (class "Default")
      (node (ref "R26") (pin "A") (pinfunction "A_A") (pintype "passive"))
      (node (ref "R27") (pin "2") (pinfunction "2_2") (pintype "passive"))
    )
    (net (code "52") (name "V+") (class "Default")
      (node (ref "C1") (pin "+") (pinfunction "+_+") (pintype "passive"))
      (node (ref "C12") (pin "1") (pinfunction "1_1") (pintype "passive"))
      (node (ref "C14") (pin "1") (pinfunction "1_1") (pintype "passive"))
      (node (ref "C22") (pin "1") (pinfunction "1_1") (pintype "passive"))
      (node (ref "C6") (pin "1") (pinfunction "1_1") (pintype "passive"))
      (node (ref "C8") (pin "1") (pinfunction "1_1") (pintype "passive"))
      (node (ref "IC2") (pin "11") (pinfunction "V+_11") (pintype "power_in"))
      (node (ref "IC4") (pin "11") (pinfunction "V+_11") (pintype "power_in"))
      (node (ref "R2") (pin "2") (pinfunction "2_2") (pintype "passive"))
      (node (ref "R4") (pin "1") (pinfunction "1_1") (pintype "passive"))
      (node (ref "V+") (pin "1") (pinfunction "1_1") (pintype "passive"))
    )
    (net (code "53") (name "V-") (class "Default")
      (node (ref "C11") (pin "2") (pinfunction "2_2") (pintype "passive"))
      (node (ref "C13") (pin "2") (pinfunction "2_2") (pintype "passive"))
      (node (ref "C2") (pin "-") (pinfunction "-_-") (pintype "passive"))
      (node (ref "C21") (pin "2") (pinfunction "2_2") (pintype "passive"))
      (node (ref "C3") (pin "2") (pinfunction "2_2") (pintype "passive"))
      (node (ref "C7") (pin "2") (pinfunction "2_2") (pintype "passive"))
      (node (ref "IC2") (pin "14") (pinfunction "V-_14") (pintype "power_in"))
      (node (ref "IC4") (pin "14") (pinfunction "V-_14") (pintype "power_in"))
      (node (ref "R1") (pin "2") (pinfunction "2_2") (pintype "passive"))
    )
    (net (code "54") (name "unconnected-(IC2-D2-Pad8)") (class "Default")
      (node (ref "IC2") (pin "8") (pinfunction "D2_8") (pintype "passive"))
    )
    (net (code "55") (name "unconnected-(IC2-S2-Pad9)") (class "Default")
      (node (ref "IC2") (pin "9") (pinfunction "S2_9") (pintype "passive"))
    )
    (net (code "56") (name "unconnected-(IC4-D2-Pad8)") (class "Default")
      (node (ref "IC4") (pin "8") (pinfunction "D2_8") (pintype "passive"))
    )
    (net (code "57") (name "unconnected-(IC4-S2-Pad9)") (class "Default")
      (node (ref "IC4") (pin "9") (pinfunction "S2_9") (pintype "passive"))
    )
    (net (code "58") (name "unconnected-(R7-S-PadS@1)") (class "Default")
      (node (ref "R7") (pin "S@1") (pinfunction "S_S@1") (pintype "passive"))
    )
    (net (code "59") (name "unconnected-(R26-S-PadS@1)") (class "Default")
      (node (ref "R26") (pin "S@1") (pinfunction "S_S@1") (pintype "passive"))
    )
  )
)
